# wrover-cam.net
KiCad netlist of a schematic drawn in EAGLE
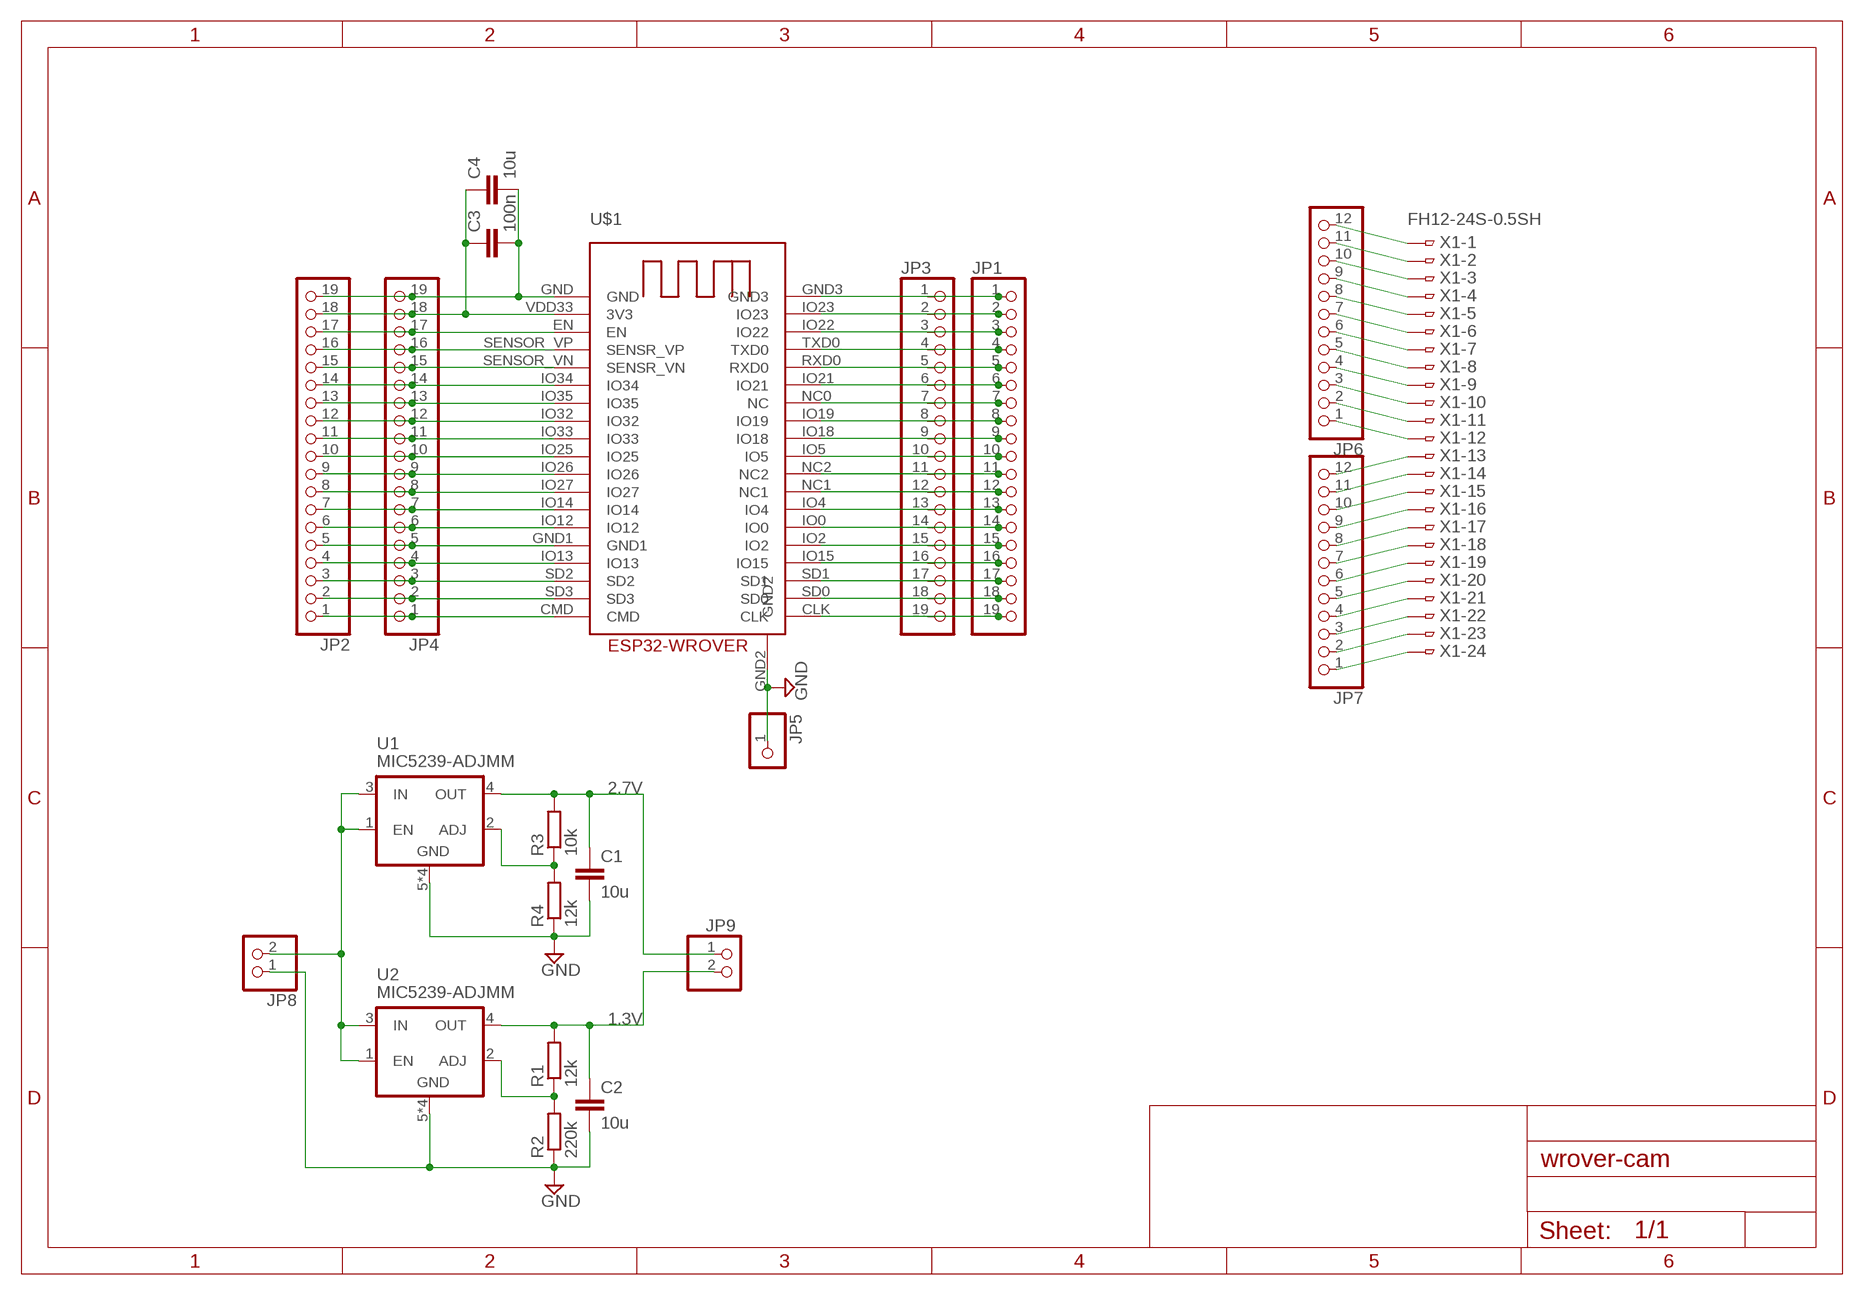
[diagram p0: schematic, sheet 1]

(export (version "E")
  (design (tool "Eeschema 10.0.6"))
  (components
    (comp (ref "C1")
      (value "10u")
      (footprint "eagle-import:C1210K")
      (libsource (lib "eagle-import") (part "C-EUC1210K"))
    )
    (comp (ref "C2")
      (value "10u")
      (footprint "eagle-import:C1210K")
      (libsource (lib "eagle-import") (part "C-EUC1210K"))
    )
    (comp (ref "C3")
      (value "100n")
      (footprint "eagle-import:C0805K")
      (libsource (lib "eagle-import") (part "C-EUC0805K"))
    )
    (comp (ref "C4")
      (value "10u")
      (footprint "eagle-import:C1210K")
      (libsource (lib "eagle-import") (part "C-EUC1210K"))
    )
    (comp (ref "JP1")
      (value "PINHD-1X19")
      (footprint "eagle-import:1X19")
      (libsource (lib "eagle-import") (part "PINHD-1X19"))
    )
    (comp (ref "JP2")
      (value "PINHD-1X19")
      (footprint "eagle-import:1X19")
      (libsource (lib "eagle-import") (part "PINHD-1X19"))
    )
    (comp (ref "JP3")
      (value "PINHD-1X19")
      (footprint "eagle-import:1X19")
      (libsource (lib "eagle-import") (part "PINHD-1X19"))
    )
    (comp (ref "JP4")
      (value "PINHD-1X19")
      (footprint "eagle-import:1X19")
      (libsource (lib "eagle-import") (part "PINHD-1X19"))
    )
    (comp (ref "JP5")
      (value "PINHD-1X1")
      (footprint "eagle-import:1X01")
      (libsource (lib "eagle-import") (part "PINHD-1X1"))
    )
    (comp (ref "JP6")
      (value "PINHD-1X12")
      (footprint "eagle-import:1X12")
      (libsource (lib "eagle-import") (part "PINHD-1X12"))
    )
    (comp (ref "JP7")
      (value "PINHD-1X12")
      (footprint "eagle-import:1X12")
      (libsource (lib "eagle-import") (part "PINHD-1X12"))
    )
    (comp (ref "JP8")
      (value "PINHD-1X2")
      (footprint "eagle-import:1X02")
      (libsource (lib "eagle-import") (part "PINHD-1X2"))
    )
    (comp (ref "JP9")
      (value "PINHD-1X2")
      (footprint "eagle-import:1X02")
      (libsource (lib "eagle-import") (part "PINHD-1X2"))
    )
    (comp (ref "R1")
      (value "12k")
      (footprint "eagle-import:R1206")
      (libsource (lib "eagle-import") (part "R-EU_R1206"))
    )
    (comp (ref "R2")
      (value "220k")
      (footprint "eagle-import:R1206")
      (libsource (lib "eagle-import") (part "R-EU_R1206"))
    )
    (comp (ref "R3")
      (value "10k")
      (footprint "eagle-import:R1206")
      (libsource (lib "eagle-import") (part "R-EU_R1206"))
    )
    (comp (ref "R4")
      (value "12k")
      (footprint "eagle-import:R1206")
      (libsource (lib "eagle-import") (part "R-EU_R1206"))
    )
    (comp (ref "U$1")
      (value "ESP32-WROVER")
      (footprint "eagle-import:ESP32-WROVER")
      (libsource (lib "eagle-import") (part "ESP32-WROVER"))
    )
    (comp (ref "U1")
      (value "MIC5239-ADJMM")
      (footprint "eagle-import:MSOP08")
      (libsource (lib "eagle-import") (part "MIC5239-ADJMM"))
    )
    (comp (ref "U2")
      (value "MIC5239-ADJMM")
      (footprint "eagle-import:MSOP08")
      (libsource (lib "eagle-import") (part "MIC5239-ADJMM"))
    )
    (comp (ref "X1")
      (value "FH12-24S-0.5SH")
      (footprint "eagle-import:FH12-24S-0.5SH")
      (fields (field (name "MPN") "FH12-24S-0.5SH(55)"))
      (libsource (lib "eagle-import") (part "FH12-24S-0.5SH"))
    )
  )
  (nets
    (net (code "1") (name "/1.3V") (class "Default")
      (node (ref "C2") (pin "1") (pinfunction "1_1") (pintype "passive"))
      (node (ref "JP9") (pin "2") (pinfunction "2_2") (pintype "passive"))
      (node (ref "R1") (pin "2") (pinfunction "2_2") (pintype "passive"))
      (node (ref "U2") (pin "4") (pinfunction "OUT_4") (pintype "passive"))
    )
    (net (code "2") (name "/2.7V") (class "Default")
      (node (ref "C1") (pin "1") (pinfunction "1_1") (pintype "passive"))
      (node (ref "JP9") (pin "1") (pinfunction "1_1") (pintype "passive"))
      (node (ref "R3") (pin "2") (pinfunction "2_2") (pintype "passive"))
      (node (ref "U1") (pin "4") (pinfunction "OUT_4") (pintype "passive"))
    )
    (net (code "3") (name "GND") (class "Default")
      (node (ref "C1") (pin "2") (pinfunction "2_2") (pintype "passive"))
      (node (ref "C2") (pin "2") (pinfunction "2_2") (pintype "passive"))
      (node (ref "JP5") (pin "1") (pinfunction "1_1") (pintype "passive"))
      (node (ref "JP8") (pin "1") (pinfunction "1_1") (pintype "passive"))
      (node (ref "R2") (pin "1") (pinfunction "1_1") (pintype "passive"))
      (node (ref "R4") (pin "1") (pinfunction "1_1") (pintype "passive"))
      (node (ref "U$1") (pin "GND2") (pinfunction "GND2_GND2") (pintype "bidirectional"))
      (node (ref "U1") (pin "5") (pinfunction "GND_5") (pintype "power_in"))
      (node (ref "U1") (pin "6") (pinfunction "GND_6") (pintype "power_in"))
      (node (ref "U1") (pin "7") (pinfunction "GND_7") (pintype "power_in"))
      (node (ref "U1") (pin "8") (pinfunction "GND_8") (pintype "power_in"))
      (node (ref "U2") (pin "5") (pinfunction "GND_5") (pintype "power_in"))
      (node (ref "U2") (pin "6") (pinfunction "GND_6") (pintype "power_in"))
      (node (ref "U2") (pin "7") (pinfunction "GND_7") (pintype "power_in"))
      (node (ref "U2") (pin "8") (pinfunction "GND_8") (pintype "power_in"))
    )
    (net (code "4") (name "Net-(C3-Pad2)") (class "Default")
      (node (ref "C3") (pin "2") (pinfunction "2_2") (pintype "passive"))
      (node (ref "C4") (pin "2") (pinfunction "2_2") (pintype "passive"))
      (node (ref "JP2") (pin "19") (pinfunction "19_19") (pintype "passive"))
      (node (ref "JP4") (pin "19") (pinfunction "19_19") (pintype "passive"))
      (node (ref "U$1") (pin "GND") (pinfunction "GND_GND") (pintype "bidirectional"))
    )
    (net (code "5") (name "Net-(JP1-Pad1)") (class "Default")
      (node (ref "JP1") (pin "1") (pinfunction "1_1") (pintype "passive"))
      (node (ref "JP3") (pin "1") (pinfunction "1_1") (pintype "passive"))
      (node (ref "U$1") (pin "GND3") (pinfunction "GND3_GND3") (pintype "bidirectional"))
    )
    (net (code "6") (name "Net-(JP1-Pad2)") (class "Default")
      (node (ref "JP1") (pin "2") (pinfunction "2_2") (pintype "passive"))
      (node (ref "JP3") (pin "2") (pinfunction "2_2") (pintype "passive"))
      (node (ref "U$1") (pin "IO23") (pinfunction "IO23_IO23") (pintype "bidirectional"))
    )
    (net (code "7") (name "Net-(JP1-Pad3)") (class "Default")
      (node (ref "JP1") (pin "3") (pinfunction "3_3") (pintype "passive"))
      (node (ref "JP3") (pin "3") (pinfunction "3_3") (pintype "passive"))
      (node (ref "U$1") (pin "IO22") (pinfunction "IO22_IO22") (pintype "bidirectional"))
    )
    (net (code "8") (name "Net-(JP1-Pad4)") (class "Default")
      (node (ref "JP1") (pin "4") (pinfunction "4_4") (pintype "passive"))
      (node (ref "JP3") (pin "4") (pinfunction "4_4") (pintype "passive"))
      (node (ref "U$1") (pin "TXD0") (pinfunction "TXD0_TXD0") (pintype "bidirectional"))
    )
    (net (code "9") (name "Net-(JP1-Pad5)") (class "Default")
      (node (ref "JP1") (pin "5") (pinfunction "5_5") (pintype "passive"))
      (node (ref "JP3") (pin "5") (pinfunction "5_5") (pintype "passive"))
      (node (ref "U$1") (pin "RXD0") (pinfunction "RXD0_RXD0") (pintype "bidirectional"))
    )
    (net (code "10") (name "Net-(JP1-Pad6)") (class "Default")
      (node (ref "JP1") (pin "6") (pinfunction "6_6") (pintype "passive"))
      (node (ref "JP3") (pin "6") (pinfunction "6_6") (pintype "passive"))
      (node (ref "U$1") (pin "IO21") (pinfunction "IO21_IO21") (pintype "bidirectional"))
    )
    (net (code "11") (name "Net-(JP1-Pad8)") (class "Default")
      (node (ref "JP1") (pin "8") (pinfunction "8_8") (pintype "passive"))
      (node (ref "JP3") (pin "8") (pinfunction "8_8") (pintype "passive"))
      (node (ref "U$1") (pin "IO19") (pinfunction "IO19_IO19") (pintype "bidirectional"))
    )
    (net (code "12") (name "Net-(JP1-Pad9)") (class "Default")
      (node (ref "JP1") (pin "9") (pinfunction "9_9") (pintype "passive"))
      (node (ref "JP3") (pin "9") (pinfunction "9_9") (pintype "passive"))
      (node (ref "U$1") (pin "IO18") (pinfunction "IO18_IO18") (pintype "bidirectional"))
    )
    (net (code "13") (name "Net-(JP1-Pad10)") (class "Default")
      (node (ref "JP1") (pin "10") (pinfunction "10_10") (pintype "passive"))
      (node (ref "JP3") (pin "10") (pinfunction "10_10") (pintype "passive"))
      (node (ref "U$1") (pin "IO5") (pinfunction "IO5_IO5") (pintype "bidirectional"))
    )
    (net (code "14") (name "Net-(JP1-Pad11)") (class "Default")
      (node (ref "JP1") (pin "11") (pinfunction "11_11") (pintype "passive"))
      (node (ref "JP3") (pin "11") (pinfunction "11_11") (pintype "passive"))
      (node (ref "U$1") (pin "NC2") (pinfunction "NC2_NC2") (pintype "bidirectional"))
    )
    (net (code "15") (name "Net-(JP1-Pad12)") (class "Default")
      (node (ref "JP1") (pin "12") (pinfunction "12_12") (pintype "passive"))
      (node (ref "JP3") (pin "12") (pinfunction "12_12") (pintype "passive"))
      (node (ref "U$1") (pin "NC1") (pinfunction "NC1_NC1") (pintype "bidirectional"))
    )
    (net (code "16") (name "Net-(JP1-Pad13)") (class "Default")
      (node (ref "JP1") (pin "13") (pinfunction "13_13") (pintype "passive"))
      (node (ref "JP3") (pin "13") (pinfunction "13_13") (pintype "passive"))
      (node (ref "U$1") (pin "IO4") (pinfunction "IO4_IO4") (pintype "bidirectional"))
    )
    (net (code "17") (name "Net-(JP1-Pad14)") (class "Default")
      (node (ref "JP1") (pin "14") (pinfunction "14_14") (pintype "passive"))
      (node (ref "JP3") (pin "14") (pinfunction "14_14") (pintype "passive"))
      (node (ref "U$1") (pin "IO0") (pinfunction "IO0_IO0") (pintype "bidirectional"))
    )
    (net (code "18") (name "Net-(JP1-Pad15)") (class "Default")
      (node (ref "JP1") (pin "15") (pinfunction "15_15") (pintype "passive"))
      (node (ref "JP3") (pin "15") (pinfunction "15_15") (pintype "passive"))
      (node (ref "U$1") (pin "IO2") (pinfunction "IO2_IO2") (pintype "bidirectional"))
    )
    (net (code "19") (name "Net-(JP1-Pad16)") (class "Default")
      (node (ref "JP1") (pin "16") (pinfunction "16_16") (pintype "passive"))
      (node (ref "JP3") (pin "16") (pinfunction "16_16") (pintype "passive"))
      (node (ref "U$1") (pin "IO15") (pinfunction "IO15_IO15") (pintype "bidirectional"))
    )
    (net (code "20") (name "Net-(JP1-Pad17)") (class "Default")
      (node (ref "JP1") (pin "17") (pinfunction "17_17") (pintype "passive"))
      (node (ref "JP3") (pin "17") (pinfunction "17_17") (pintype "passive"))
      (node (ref "U$1") (pin "SD1") (pinfunction "SD1_SD1") (pintype "bidirectional"))
    )
    (net (code "21") (name "Net-(JP1-Pad18)") (class "Default")
      (node (ref "JP1") (pin "18") (pinfunction "18_18") (pintype "passive"))
      (node (ref "JP3") (pin "18") (pinfunction "18_18") (pintype "passive"))
      (node (ref "U$1") (pin "SD0") (pinfunction "SD0_SD0") (pintype "bidirectional"))
    )
    (net (code "22") (name "Net-(JP1-Pad19)") (class "Default")
      (node (ref "JP1") (pin "19") (pinfunction "19_19") (pintype "passive"))
      (node (ref "JP3") (pin "19") (pinfunction "19_19") (pintype "passive"))
      (node (ref "U$1") (pin "CLK") (pinfunction "CLK_CLK") (pintype "bidirectional"))
    )
    (net (code "23") (name "Net-(JP2-Pad1)") (class "Default")
      (node (ref "JP2") (pin "1") (pinfunction "1_1") (pintype "passive"))
      (node (ref "JP4") (pin "1") (pinfunction "1_1") (pintype "passive"))
      (node (ref "U$1") (pin "CMD") (pinfunction "CMD_CMD") (pintype "bidirectional"))
    )
    (net (code "24") (name "Net-(JP2-Pad2)") (class "Default")
      (node (ref "JP2") (pin "2") (pinfunction "2_2") (pintype "passive"))
      (node (ref "JP4") (pin "2") (pinfunction "2_2") (pintype "passive"))
      (node (ref "U$1") (pin "SD3") (pinfunction "SD3_SD3") (pintype "bidirectional"))
    )
    (net (code "25") (name "Net-(JP2-Pad3)") (class "Default")
      (node (ref "JP2") (pin "3") (pinfunction "3_3") (pintype "passive"))
      (node (ref "JP4") (pin "3") (pinfunction "3_3") (pintype "passive"))
      (node (ref "U$1") (pin "SD2") (pinfunction "SD2_SD2") (pintype "bidirectional"))
    )
    (net (code "26") (name "Net-(JP2-Pad4)") (class "Default")
      (node (ref "JP2") (pin "4") (pinfunction "4_4") (pintype "passive"))
      (node (ref "JP4") (pin "4") (pinfunction "4_4") (pintype "passive"))
      (node (ref "U$1") (pin "IO13") (pinfunction "IO13_IO13") (pintype "bidirectional"))
    )
    (net (code "27") (name "Net-(JP2-Pad5)") (class "Default")
      (node (ref "JP2") (pin "5") (pinfunction "5_5") (pintype "passive"))
      (node (ref "JP4") (pin "5") (pinfunction "5_5") (pintype "passive"))
      (node (ref "U$1") (pin "GND1") (pinfunction "GND1_GND1") (pintype "bidirectional"))
    )
    (net (code "28") (name "Net-(JP2-Pad6)") (class "Default")
      (node (ref "JP2") (pin "6") (pinfunction "6_6") (pintype "passive"))
      (node (ref "JP4") (pin "6") (pinfunction "6_6") (pintype "passive"))
      (node (ref "U$1") (pin "IO12") (pinfunction "IO12_IO12") (pintype "bidirectional"))
    )
    (net (code "29") (name "Net-(JP2-Pad7)") (class "Default")
      (node (ref "JP2") (pin "7") (pinfunction "7_7") (pintype "passive"))
      (node (ref "JP4") (pin "7") (pinfunction "7_7") (pintype "passive"))
      (node (ref "U$1") (pin "IO14") (pinfunction "IO14_IO14") (pintype "bidirectional"))
    )
    (net (code "30") (name "Net-(JP2-Pad8)") (class "Default")
      (node (ref "JP2") (pin "8") (pinfunction "8_8") (pintype "passive"))
      (node (ref "JP4") (pin "8") (pinfunction "8_8") (pintype "passive"))
      (node (ref "U$1") (pin "IO27") (pinfunction "IO27_IO27") (pintype "bidirectional"))
    )
    (net (code "31") (name "Net-(JP2-Pad9)") (class "Default")
      (node (ref "JP2") (pin "9") (pinfunction "9_9") (pintype "passive"))
      (node (ref "JP4") (pin "9") (pinfunction "9_9") (pintype "passive"))
      (node (ref "U$1") (pin "IO26") (pinfunction "IO26_IO26") (pintype "bidirectional"))
    )
    (net (code "32") (name "Net-(JP2-Pad10)") (class "Default")
      (node (ref "JP2") (pin "10") (pinfunction "10_10") (pintype "passive"))
      (node (ref "JP4") (pin "10") (pinfunction "10_10") (pintype "passive"))
      (node (ref "U$1") (pin "IO25") (pinfunction "IO25_IO25") (pintype "bidirectional"))
    )
    (net (code "33") (name "Net-(JP2-Pad11)") (class "Default")
      (node (ref "JP2") (pin "11") (pinfunction "11_11") (pintype "passive"))
      (node (ref "JP4") (pin "11") (pinfunction "11_11") (pintype "passive"))
      (node (ref "U$1") (pin "IO33") (pinfunction "IO33_IO33") (pintype "bidirectional"))
    )
    (net (code "34") (name "Net-(JP2-Pad12)") (class "Default")
      (node (ref "JP2") (pin "12") (pinfunction "12_12") (pintype "passive"))
      (node (ref "JP4") (pin "12") (pinfunction "12_12") (pintype "passive"))
      (node (ref "U$1") (pin "IO32") (pinfunction "IO32_IO32") (pintype "bidirectional"))
    )
    (net (code "35") (name "Net-(JP2-Pad13)") (class "Default")
      (node (ref "JP2") (pin "13") (pinfunction "13_13") (pintype "passive"))
      (node (ref "JP4") (pin "13") (pinfunction "13_13") (pintype "passive"))
      (node (ref "U$1") (pin "IO35") (pinfunction "IO35_IO35") (pintype "bidirectional"))
    )
    (net (code "36") (name "Net-(JP2-Pad14)") (class "Default")
      (node (ref "JP2") (pin "14") (pinfunction "14_14") (pintype "passive"))
      (node (ref "JP4") (pin "14") (pinfunction "14_14") (pintype "passive"))
      (node (ref "U$1") (pin "IO34") (pinfunction "IO34_IO34") (pintype "bidirectional"))
    )
    (net (code "37") (name "Net-(JP2-Pad17)") (class "Default")
      (node (ref "JP2") (pin "17") (pinfunction "17_17") (pintype "passive"))
      (node (ref "JP4") (pin "17") (pinfunction "17_17") (pintype "passive"))
      (node (ref "U$1") (pin "EN") (pinfunction "EN_EN") (pintype "bidirectional"))
    )
    (net (code "38") (name "Net-(JP6-Pad12)") (class "Default")
      (node (ref "JP6") (pin "12") (pinfunction "12_12") (pintype "passive"))
      (node (ref "X1") (pin "1") (pinfunction "1_1") (pintype "passive"))
    )
    (net (code "39") (name "Net-(U$1-3V3)") (class "Default")
      (node (ref "C3") (pin "1") (pinfunction "1_1") (pintype "passive"))
      (node (ref "C4") (pin "1") (pinfunction "1_1") (pintype "passive"))
      (node (ref "JP2") (pin "18") (pinfunction "18_18") (pintype "passive"))
      (node (ref "JP4") (pin "18") (pinfunction "18_18") (pintype "passive"))
      (node (ref "U$1") (pin "VDD33") (pinfunction "3V3_VDD33") (pintype "bidirectional"))
    )
    (net (code "40") (name "Net-(U$1-NC)") (class "Default")
      (node (ref "JP1") (pin "7") (pinfunction "7_7") (pintype "passive"))
      (node (ref "JP3") (pin "7") (pinfunction "7_7") (pintype "passive"))
      (node (ref "U$1") (pin "NC0") (pinfunction "NC_NC0") (pintype "bidirectional"))
    )
    (net (code "41") (name "Net-(U$1-SENSR_VN)") (class "Default")
      (node (ref "JP2") (pin "15") (pinfunction "15_15") (pintype "passive"))
      (node (ref "JP4") (pin "15") (pinfunction "15_15") (pintype "passive"))
      (node (ref "U$1") (pin "SENSOR_VN") (pinfunction "SENSR_VN_SENSOR_VN") (pintype "bidirectional"))
    )
    (net (code "42") (name "Net-(U$1-SENSR_VP)") (class "Default")
      (node (ref "JP2") (pin "16") (pinfunction "16_16") (pintype "passive"))
      (node (ref "JP4") (pin "16") (pinfunction "16_16") (pintype "passive"))
      (node (ref "U$1") (pin "SENSOR_VP") (pinfunction "SENSR_VP_SENSOR_VP") (pintype "bidirectional"))
    )
    (net (code "43") (name "Net-(U1-ADJ)") (class "Default")
      (node (ref "R3") (pin "1") (pinfunction "1_1") (pintype "passive"))
      (node (ref "R4") (pin "2") (pinfunction "2_2") (pintype "passive"))
      (node (ref "U1") (pin "2") (pinfunction "ADJ_2") (pintype "passive"))
    )
    (net (code "44") (name "Net-(U1-EN)") (class "Default")
      (node (ref "JP8") (pin "2") (pinfunction "2_2") (pintype "passive"))
      (node (ref "U1") (pin "1") (pinfunction "EN_1") (pintype "input"))
      (node (ref "U1") (pin "3") (pinfunction "IN_3") (pintype "input"))
      (node (ref "U2") (pin "1") (pinfunction "EN_1") (pintype "input"))
      (node (ref "U2") (pin "3") (pinfunction "IN_3") (pintype "input"))
    )
    (net (code "45") (name "Net-(U2-ADJ)") (class "Default")
      (node (ref "R1") (pin "1") (pinfunction "1_1") (pintype "passive"))
      (node (ref "R2") (pin "2") (pinfunction "2_2") (pintype "passive"))
      (node (ref "U2") (pin "2") (pinfunction "ADJ_2") (pintype "passive"))
    )
    (net (code "46") (name "Net-(X1B-1)") (class "Default")
      (node (ref "JP6") (pin "3") (pinfunction "3_3") (pintype "passive"))
      (node (ref "X1") (pin "10") (pinfunction "1_10") (pintype "passive"))
    )
    (net (code "47") (name "Net-(X1C-1)") (class "Default")
      (node (ref "JP6") (pin "2") (pinfunction "2_2") (pintype "passive"))
      (node (ref "X1") (pin "11") (pinfunction "1_11") (pintype "passive"))
    )
    (net (code "48") (name "Net-(X1D-1)") (class "Default")
      (node (ref "JP6") (pin "1") (pinfunction "1_1") (pintype "passive"))
      (node (ref "X1") (pin "12") (pinfunction "1_12") (pintype "passive"))
    )
    (net (code "49") (name "Net-(X1E-1)") (class "Default")
      (node (ref "JP7") (pin "12") (pinfunction "12_12") (pintype "passive"))
      (node (ref "X1") (pin "13") (pinfunction "1_13") (pintype "passive"))
    )
    (net (code "50") (name "Net-(X1F-1)") (class "Default")
      (node (ref "JP7") (pin "11") (pinfunction "11_11") (pintype "passive"))
      (node (ref "X1") (pin "14") (pinfunction "1_14") (pintype "passive"))
    )
    (net (code "51") (name "Net-(X1G-1)") (class "Default")
      (node (ref "JP7") (pin "10") (pinfunction "10_10") (pintype "passive"))
      (node (ref "X1") (pin "15") (pinfunction "1_15") (pintype "passive"))
    )
    (net (code "52") (name "Net-(X1H-1)") (class "Default")
      (node (ref "JP7") (pin "9") (pinfunction "9_9") (pintype "passive"))
      (node (ref "X1") (pin "16") (pinfunction "1_16") (pintype "passive"))
    )
    (net (code "53") (name "Net-(X1I-1)") (class "Default")
      (node (ref "JP7") (pin "8") (pinfunction "8_8") (pintype "passive"))
      (node (ref "X1") (pin "17") (pinfunction "1_17") (pintype "passive"))
    )
    (net (code "54") (name "Net-(X1J-1)") (class "Default")
      (node (ref "JP7") (pin "7") (pinfunction "7_7") (pintype "passive"))
      (node (ref "X1") (pin "18") (pinfunction "1_18") (pintype "passive"))
    )
    (net (code "55") (name "Net-(X1K-1)") (class "Default")
      (node (ref "JP7") (pin "6") (pinfunction "6_6") (pintype "passive"))
      (node (ref "X1") (pin "19") (pinfunction "1_19") (pintype "passive"))
    )
    (net (code "56") (name "Net-(X1L-1)") (class "Default")
      (node (ref "JP6") (pin "11") (pinfunction "11_11") (pintype "passive"))
      (node (ref "X1") (pin "2") (pinfunction "1_2") (pintype "passive"))
    )
    (net (code "57") (name "Net-(X1M-1)") (class "Default")
      (node (ref "JP7") (pin "5") (pinfunction "5_5") (pintype "passive"))
      (node (ref "X1") (pin "20") (pinfunction "1_20") (pintype "passive"))
    )
    (net (code "58") (name "Net-(X1N-1)") (class "Default")
      (node (ref "JP7") (pin "4") (pinfunction "4_4") (pintype "passive"))
      (node (ref "X1") (pin "21") (pinfunction "1_21") (pintype "passive"))
    )
    (net (code "59") (name "Net-(X1O-1)") (class "Default")
      (node (ref "JP7") (pin "3") (pinfunction "3_3") (pintype "passive"))
      (node (ref "X1") (pin "22") (pinfunction "1_22") (pintype "passive"))
    )
    (net (code "60") (name "Net-(X1P-1)") (class "Default")
      (node (ref "JP7") (pin "2") (pinfunction "2_2") (pintype "passive"))
      (node (ref "X1") (pin "23") (pinfunction "1_23") (pintype "passive"))
    )
    (net (code "61") (name "Net-(X1Q-1)") (class "Default")
      (node (ref "JP7") (pin "1") (pinfunction "1_1") (pintype "passive"))
      (node (ref "X1") (pin "24") (pinfunction "1_24") (pintype "passive"))
    )
    (net (code "62") (name "Net-(X1R-1)") (class "Default")
      (node (ref "JP6") (pin "10") (pinfunction "10_10") (pintype "passive"))
      (node (ref "X1") (pin "3") (pinfunction "1_3") (pintype "passive"))
    )
    (net (code "63") (name "Net-(X1S-1)") (class "Default")
      (node (ref "JP6") (pin "9") (pinfunction "9_9") (pintype "passive"))
      (node (ref "X1") (pin "4") (pinfunction "1_4") (pintype "passive"))
    )
    (net (code "64") (name "Net-(X1T-1)") (class "Default")
      (node (ref "JP6") (pin "8") (pinfunction "8_8") (pintype "passive"))
      (node (ref "X1") (pin "5") (pinfunction "1_5") (pintype "passive"))
    )
    (net (code "65") (name "Net-(X1U-1)") (class "Default")
      (node (ref "JP6") (pin "7") (pinfunction "7_7") (pintype "passive"))
      (node (ref "X1") (pin "6") (pinfunction "1_6") (pintype "passive"))
    )
    (net (code "66") (name "Net-(X1V-1)") (class "Default")
      (node (ref "JP6") (pin "6") (pinfunction "6_6") (pintype "passive"))
      (node (ref "X1") (pin "7") (pinfunction "1_7") (pintype "passive"))
    )
    (net (code "67") (name "Net-(X1W-1)") (class "Default")
      (node (ref "JP6") (pin "5") (pinfunction "5_5") (pintype "passive"))
      (node (ref "X1") (pin "8") (pinfunction "1_8") (pintype "passive"))
    )
    (net (code "68") (name "Net-(X1X-1)") (class "Default")
      (node (ref "JP6") (pin "4") (pinfunction "4_4") (pintype "passive"))
      (node (ref "X1") (pin "9") (pinfunction "1_9") (pintype "passive"))
    )
  )
)
